# OpticalSensor.net
KiCad netlist of a schematic drawn in Altium Designer
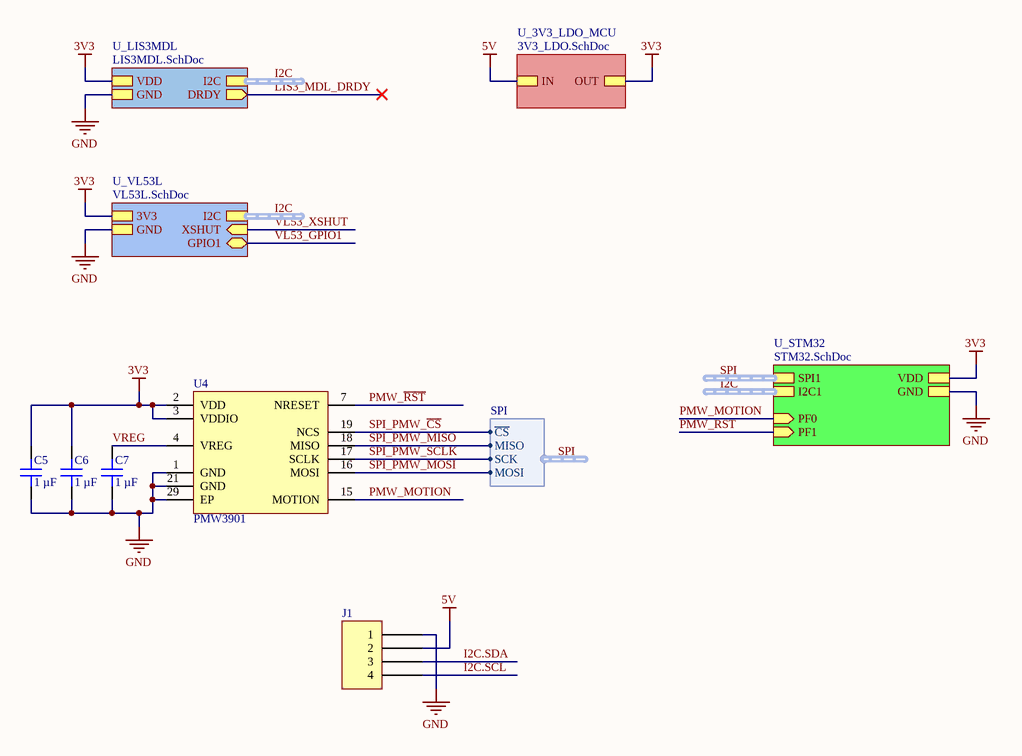
[diagram p0: OpticalSensor.SchDoc]

(export (version "E")
  (design (tool "Eeschema 10.0.6"))
  (components
    (comp (ref "C5")
      (value "1 µF")
      (footprint "CAP 0402_1005")
      (description "CAP CER 0.1UF 16V X7R 0402")
      (fields (field (name "PART NUMBER") "C0402C104K4RACAUTO") (field (name "MANUFACTURER") "KEMET"))
      (libsource (lib "Celestial Altium Library - altium_library") (part "Capacitor"))
    )
    (comp (ref "C6")
      (value "1 µF")
      (footprint "CAP 0402_1005")
      (description "CAP CER 0.1UF 16V X7R 0402")
      (fields (field (name "PART NUMBER") "C0402C104K4RACAUTO") (field (name "MANUFACTURER") "KEMET"))
      (libsource (lib "Celestial Altium Library - altium_library") (part "Capacitor"))
    )
    (comp (ref "C7")
      (value "1 µF")
      (footprint "CAP 0402_1005")
      (description "CAP CER 0.1UF 16V X7R 0402")
      (fields (field (name "PART NUMBER") "C0402C104K4RACAUTO") (field (name "MANUFACTURER") "KEMET"))
      (libsource (lib "Celestial Altium Library - altium_library") (part "Capacitor"))
    )
    (comp (ref "J1")
      (value "SM04B-SRSS-TB(LF)(SN)")
      (footprint "JST SM04B-SRSS-TB")
      (description "CONN HEADER SMD R/A 4POS 1MM")
      (fields (field (name "MANUFACTURER") "JST Sales America Inc."))
      (libsource (lib "Celestial Altium Library - altium_library") (part "4 Pin"))
    )
    (comp (ref "U4")
      (value "PMW3901")
      (footprint "PMW3901")
      (description "PMW3901. Optical Flow Sensor")
      (libsource (lib "IC") (part "PMW3901"))
    )
  )
  (nets
    (net (code "4") (name "/I2C.SCL") (class "Default")
      (node (ref "J1") (pin "4") (pinfunction "4_4") (pintype "passive"))
    )
    (net (code "5") (name "/I2C.SDA") (class "Default")
      (node (ref "J1") (pin "3") (pinfunction "3_3") (pintype "passive"))
    )
    (net (code "7") (name "/PMW_MOTION") (class "Default")
      (node (ref "U4") (pin "15") (pinfunction "MOTION_15") (pintype "passive"))
    )
    (net (code "8") (name "/PMW_~{RST}") (class "Default")
      (node (ref "U4") (pin "7") (pinfunction "NRESET_7") (pintype "passive"))
    )
    (net (code "9") (name "/SPI_PMW_MISO") (class "Default")
      (node (ref "U4") (pin "18") (pinfunction "MISO_18") (pintype "passive"))
    )
    (net (code "10") (name "/SPI_PMW_MOSI") (class "Default")
      (node (ref "U4") (pin "16") (pinfunction "MOSI_16") (pintype "passive"))
    )
    (net (code "11") (name "/SPI_PMW_SCLK") (class "Default")
      (node (ref "U4") (pin "17") (pinfunction "SCLK_17") (pintype "passive"))
    )
    (net (code "12") (name "/SPI_PMW_~{CS}") (class "Default")
      (node (ref "U4") (pin "19") (pinfunction "NCS_19") (pintype "passive"))
    )
    (net (code "16") (name "/VREG") (class "Default")
      (node (ref "C7") (pin "2") (pinfunction "2_2") (pintype "passive"))
      (node (ref "U4") (pin "4") (pinfunction "VREG_4") (pintype "passive"))
    )
    (net (code "19") (name "3V3") (class "Default")
      (node (ref "C5") (pin "2") (pinfunction "2_2") (pintype "passive"))
      (node (ref "C6") (pin "2") (pinfunction "2_2") (pintype "passive"))
      (node (ref "U4") (pin "2") (pinfunction "VDD_2") (pintype "passive"))
      (node (ref "U4") (pin "3") (pinfunction "VDDIO_3") (pintype "passive"))
    )
    (net (code "20") (name "5V") (class "Default")
      (node (ref "J1") (pin "2") (pinfunction "2_2") (pintype "passive"))
    )
    (net (code "21") (name "GND") (class "Default")
      (node (ref "C5") (pin "1") (pinfunction "1_1") (pintype "passive"))
      (node (ref "C6") (pin "1") (pinfunction "1_1") (pintype "passive"))
      (node (ref "C7") (pin "1") (pinfunction "1_1") (pintype "passive"))
      (node (ref "J1") (pin "1") (pinfunction "1_1") (pintype "passive"))
      (node (ref "U4") (pin "1") (pinfunction "GND_1") (pintype "passive"))
      (node (ref "U4") (pin "21") (pinfunction "GND_21") (pintype "passive"))
      (node (ref "U4") (pin "29") (pinfunction "EP_29") (pintype "passive"))
    )
  )
)
